# motadora.net
KiCad netlist of a schematic drawn in EAGLE
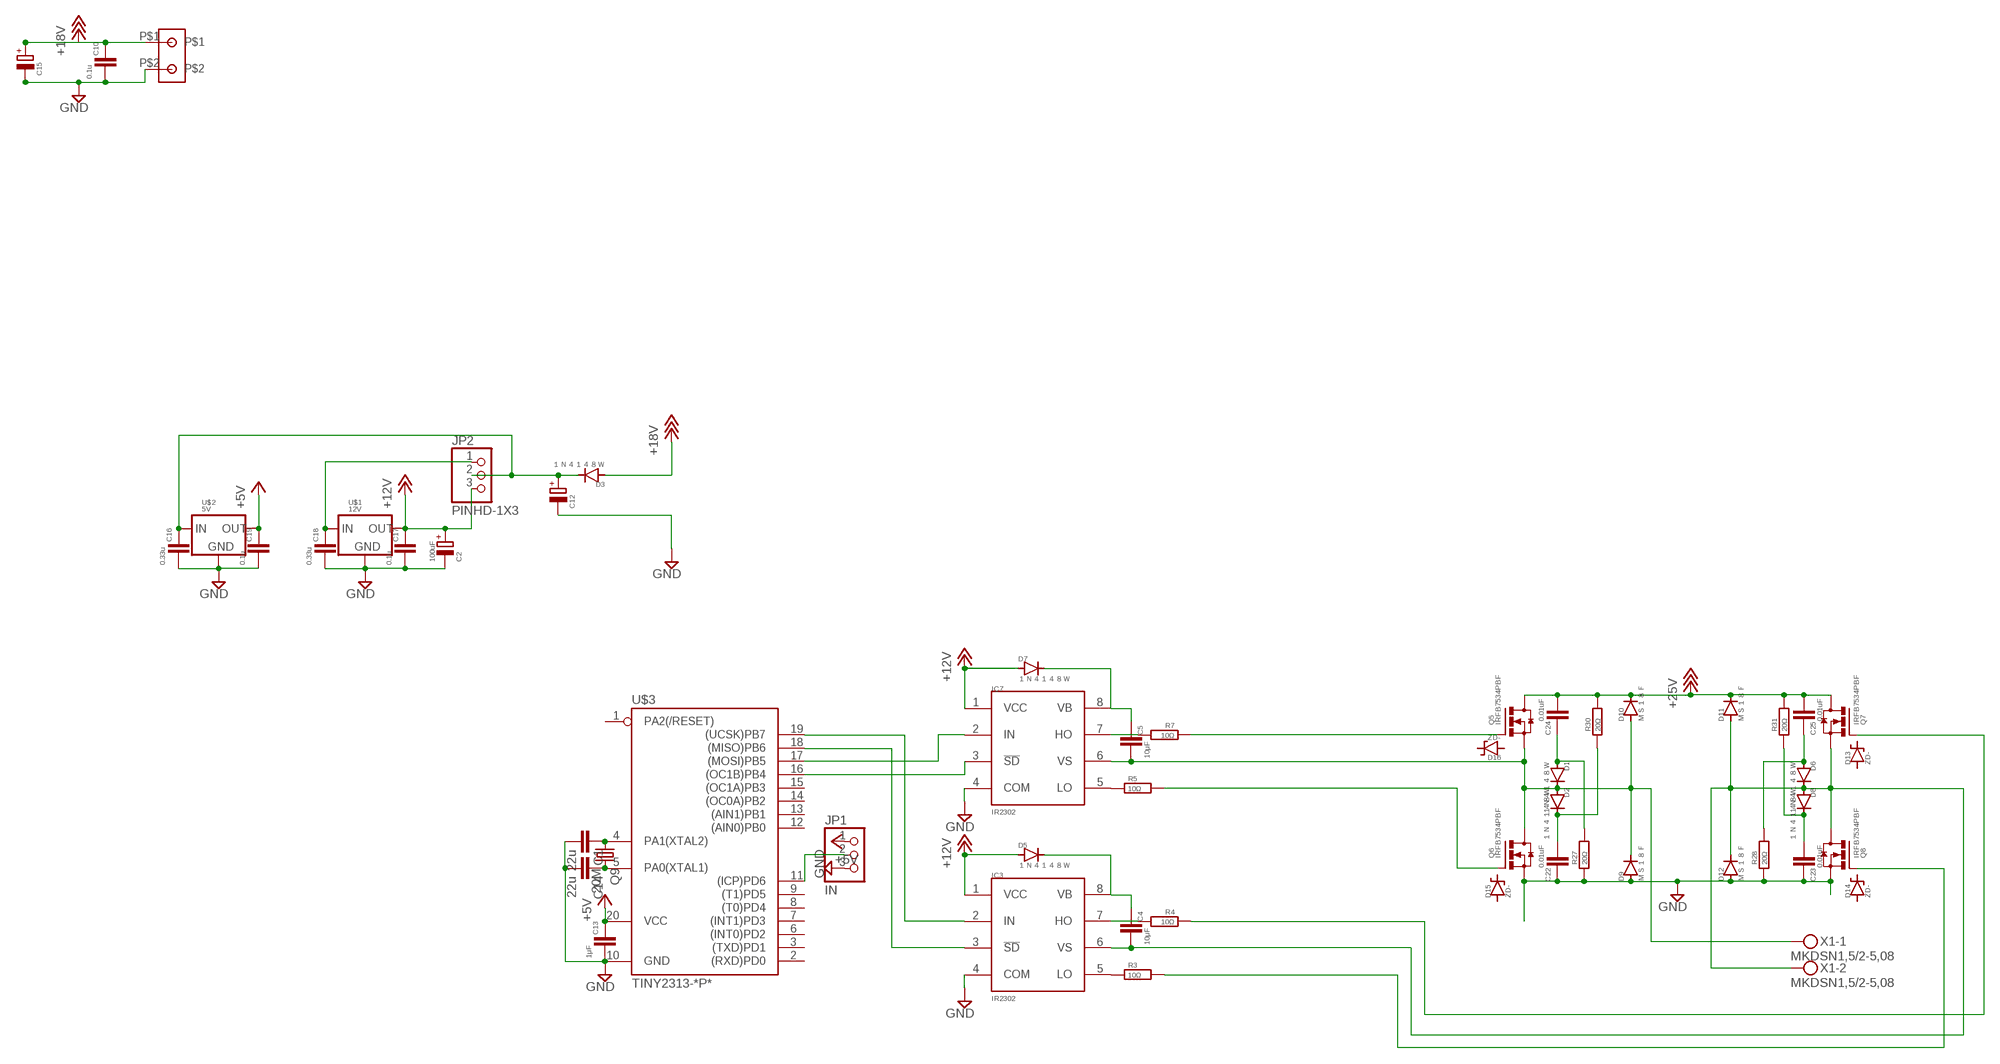
[diagram p0: schematic, sheet 1]

(export (version "E")
  (design (tool "Eeschema 10.0.6"))
  (components
    (comp (ref "C1")
      (value "22u")
      (footprint "eagle-import:C025-024X044")
      (libsource (lib "eagle-import") (part "_rcl_C-EU025-024X044"))
    )
    (comp (ref "C2")
      (value "100uF")
      (footprint "eagle-import:E2,5-7")
      (libsource (lib "eagle-import") (part "CPOL-EUE2.5-7"))
    )
    (comp (ref "C4")
      (value "10μF")
      (footprint "eagle-import:C050-024X044")
      (libsource (lib "eagle-import") (part "C-EU050-024X044"))
    )
    (comp (ref "C5")
      (value "10μF")
      (footprint "eagle-import:C050-024X044")
      (libsource (lib "eagle-import") (part "C-EU050-024X044"))
    )
    (comp (ref "C10")
      (value "0.1u")
      (footprint "eagle-import:2012")
      (libsource (lib "eagle-import") (part "_diode2_C-2012"))
    )
    (comp (ref "C12")
      (value "CPOL-EUE2.5-7")
      (footprint "eagle-import:E2,5-7")
      (libsource (lib "eagle-import") (part "CPOL-EUE2.5-7"))
    )
    (comp (ref "C13")
      (value "1μF")
      (footprint "eagle-import:C050-024X044")
      (libsource (lib "eagle-import") (part "C-EU050-024X044"))
    )
    (comp (ref "C14")
      (value "22u")
      (footprint "eagle-import:C025-024X044")
      (libsource (lib "eagle-import") (part "_rcl_C-EU025-024X044"))
    )
    (comp (ref "C15")
      (value "CPOL-EUE2.5-7")
      (footprint "eagle-import:E2,5-7")
      (libsource (lib "eagle-import") (part "CPOL-EUE2.5-7"))
    )
    (comp (ref "C16")
      (value "0.33u")
      (footprint "eagle-import:2012")
      (libsource (lib "eagle-import") (part "C-2012"))
    )
    (comp (ref "C17")
      (value "0.1u")
      (footprint "eagle-import:2012")
      (libsource (lib "eagle-import") (part "C-2012"))
    )
    (comp (ref "C18")
      (value "0.33u")
      (footprint "eagle-import:2012")
      (libsource (lib "eagle-import") (part "C-2012"))
    )
    (comp (ref "C19")
      (value "0.1u")
      (footprint "eagle-import:2012")
      (libsource (lib "eagle-import") (part "C-2012"))
    )
    (comp (ref "C22")
      (value "0.01uF")
      (footprint "eagle-import:2012")
      (libsource (lib "eagle-import") (part "C2012"))
    )
    (comp (ref "C23")
      (value "0.01uF")
      (footprint "eagle-import:2012")
      (libsource (lib "eagle-import") (part "_diode2_C-2012"))
    )
    (comp (ref "C24")
      (value "0.01uF")
      (footprint "eagle-import:2012")
      (libsource (lib "eagle-import") (part "C2012"))
    )
    (comp (ref "C25")
      (value "0.01uF")
      (footprint "eagle-import:2012")
      (libsource (lib "eagle-import") (part "_diode2_C-2012"))
    )
    (comp (ref "D1")
      (value "１Ｎ４１４８Ｗ")
      (footprint "eagle-import:SOD123")
      (libsource (lib "eagle-import") (part "D-SOD123"))
    )
    (comp (ref "D2")
      (value "１Ｎ４１４８Ｗ")
      (footprint "eagle-import:SOD123")
      (libsource (lib "eagle-import") (part "D-SOD123"))
    )
    (comp (ref "D3")
      (value "１Ｎ４１４８Ｗ")
      (footprint "eagle-import:D-7.5")
      (libsource (lib "eagle-import") (part "DIODE-D-7.5"))
    )
    (comp (ref "D5")
      (value "１Ｎ４１４８Ｗ")
      (footprint "eagle-import:D-7.5")
      (libsource (lib "eagle-import") (part "DIODE-D-7.5"))
    )
    (comp (ref "D6")
      (value "１Ｎ４１４８Ｗ")
      (footprint "eagle-import:SOD123")
      (libsource (lib "eagle-import") (part "D-SOD123"))
    )
    (comp (ref "D7")
      (value "１Ｎ４１４８Ｗ")
      (footprint "eagle-import:D-7.5")
      (libsource (lib "eagle-import") (part "DIODE-D-7.5"))
    )
    (comp (ref "D8")
      (value "１Ｎ４１４８Ｗ")
      (footprint "eagle-import:SOD123")
      (libsource (lib "eagle-import") (part "D-SOD123"))
    )
    (comp (ref "D9")
      (value "ＭＳ１８Ｆ")
      (footprint "eagle-import:^MS18F")
      (libsource (lib "eagle-import") (part "D-^MS18F"))
    )
    (comp (ref "D10")
      (value "ＭＳ１８Ｆ")
      (footprint "eagle-import:^MS18F")
      (libsource (lib "eagle-import") (part "D-^MS18F"))
    )
    (comp (ref "D11")
      (value "ＭＳ１８Ｆ")
      (footprint "eagle-import:^MS18F")
      (libsource (lib "eagle-import") (part "D-^MS18F"))
    )
    (comp (ref "D12")
      (value "ＭＳ１８Ｆ")
      (footprint "eagle-import:^MS18F")
      (libsource (lib "eagle-import") (part "D-^MS18F"))
    )
    (comp (ref "D13")
      (value "ZD-")
      (footprint "eagle-import:^U1ZB")
      (libsource (lib "eagle-import") (part "ZD-"))
    )
    (comp (ref "D14")
      (value "ZD-")
      (footprint "eagle-import:^U1ZB")
      (libsource (lib "eagle-import") (part "ZD-"))
    )
    (comp (ref "D15")
      (value "ZD-")
      (footprint "eagle-import:^U1ZB")
      (libsource (lib "eagle-import") (part "ZD-"))
    )
    (comp (ref "D16")
      (value "ZD-")
      (footprint "eagle-import:^U1ZB")
      (libsource (lib "eagle-import") (part "ZD-"))
    )
    (comp (ref "IC3")
      (value "IR2302")
      (footprint "eagle-import:DIL08")
      (libsource (lib "eagle-import") (part "IR2302IR2302"))
    )
    (comp (ref "IC7")
      (value "IR2302")
      (footprint "eagle-import:DIL08")
      (libsource (lib "eagle-import") (part "IR2302IR2302"))
    )
    (comp (ref "JP1")
      (value "IN")
      (footprint "eagle-import:1X03")
      (libsource (lib "eagle-import") (part "PINHD-1X3"))
    )
    (comp (ref "JP2")
      (value "PINHD-1X3")
      (footprint "eagle-import:1X03")
      (libsource (lib "eagle-import") (part "PINHD-1X3"))
    )
    (comp (ref "Q5")
      (value "IRFB7534PBF")
      (footprint "eagle-import:D2PACK")
      (libsource (lib "eagle-import") (part "MOS-FET_N(D2PACK)"))
    )
    (comp (ref "Q6")
      (value "IRFB7534PBF")
      (footprint "eagle-import:D2PACK")
      (libsource (lib "eagle-import") (part "MOS-FET_N(D2PACK)"))
    )
    (comp (ref "Q7")
      (value "IRFB7534PBF")
      (footprint "eagle-import:D2PACK")
      (libsource (lib "eagle-import") (part "MOS-FET_N(D2PACK)"))
    )
    (comp (ref "Q8")
      (value "IRFB7534PBF")
      (footprint "eagle-import:D2PACK")
      (libsource (lib "eagle-import") (part "MOS-FET_N(D2PACK)"))
    )
    (comp (ref "Q9")
      (value "20M")
      (footprint "eagle-import:HC49_S")
      (libsource (lib "eagle-import") (part "CRYSTALHC49S"))
    )
    (comp (ref "R3")
      (value "10Ω")
      (footprint "eagle-import:2012")
      (libsource (lib "eagle-import") (part "R-"))
    )
    (comp (ref "R4")
      (value "10Ω")
      (footprint "eagle-import:2012")
      (libsource (lib "eagle-import") (part "R-"))
    )
    (comp (ref "R5")
      (value "10Ω")
      (footprint "eagle-import:2012")
      (libsource (lib "eagle-import") (part "R-"))
    )
    (comp (ref "R7")
      (value "10Ω")
      (footprint "eagle-import:2012")
      (libsource (lib "eagle-import") (part "R-"))
    )
    (comp (ref "R27")
      (value "20Ω")
      (footprint "eagle-import:2012")
      (libsource (lib "eagle-import") (part "R-"))
    )
    (comp (ref "R28")
      (value "20Ω")
      (footprint "eagle-import:2012")
      (libsource (lib "eagle-import") (part "R-"))
    )
    (comp (ref "R30")
      (value "20Ω")
      (footprint "eagle-import:2012")
      (libsource (lib "eagle-import") (part "R-"))
    )
    (comp (ref "R31")
      (value "20Ω")
      (footprint "eagle-import:2012")
      (libsource (lib "eagle-import") (part "R-"))
    )
    (comp (ref "T1")
      (value "TANSIDAI")
      (footprint "eagle-import:A")
      (libsource (lib "eagle-import") (part "TANSIDAI"))
    )
    (comp (ref "U$1")
      (value "12V")
      (footprint "eagle-import:SOT-89")
      (libsource (lib "eagle-import") (part "V-REG(SOT-89)"))
    )
    (comp (ref "U$2")
      (value "5V")
      (footprint "eagle-import:SOT-89")
      (libsource (lib "eagle-import") (part "V-REG(SOT-89)"))
    )
    (comp (ref "U$3")
      (value "TINY2313-*P*")
      (footprint "eagle-import:DIL20")
      (libsource (lib "eagle-import") (part "TINY2313-P"))
    )
    (comp (ref "X1")
      (value "MKDSN1,5/2-5,08")
      (footprint "eagle-import:MKDSN1,5_2-5,08")
      (fields (field (name "MPN") "MKDSN 1,5/2-5.08"))
      (libsource (lib "eagle-import") (part "MKDSN1,5/2-5,08"))
    )
  )
  (nets
    (net (code "1") (name "+5V") (class "Default")
      (node (ref "C13") (pin "1") (pinfunction "1_1") (pintype "passive"))
      (node (ref "C19") (pin "1") (pinfunction "1_1") (pintype "passive"))
      (node (ref "JP1") (pin "1") (pinfunction "1_1") (pintype "passive"))
      (node (ref "U$2") (pin "1") (pinfunction "OUT_1") (pintype "passive"))
      (node (ref "U$3") (pin "20") (pinfunction "VCC_20") (pintype "power_in"))
    )
    (net (code "2") (name "+12V") (class "Default")
      (node (ref "C17") (pin "1") (pinfunction "1_1") (pintype "passive"))
      (node (ref "C2") (pin "+") (pinfunction "+_+") (pintype "passive"))
      (node (ref "D5") (pin "A") (pinfunction "A_A") (pintype "passive"))
      (node (ref "D7") (pin "A") (pinfunction "A_A") (pintype "passive"))
      (node (ref "IC3") (pin "1") (pinfunction "VCC_1") (pintype "bidirectional"))
      (node (ref "IC7") (pin "1") (pinfunction "VCC_1") (pintype "bidirectional"))
      (node (ref "JP2") (pin "3") (pinfunction "3_3") (pintype "passive"))
      (node (ref "U$1") (pin "1") (pinfunction "OUT_1") (pintype "passive"))
    )
    (net (code "3") (name "+18V") (class "Default")
      (node (ref "C10") (pin "1") (pinfunction "1_1") (pintype "passive"))
      (node (ref "C15") (pin "+") (pinfunction "+_+") (pintype "passive"))
      (node (ref "C24") (pin "2") (pinfunction "2_2") (pintype "passive"))
      (node (ref "C25") (pin "2") (pinfunction "2_2") (pintype "passive"))
      (node (ref "D10") (pin "CATHODE") (pinfunction "C_CATHODE") (pintype "passive"))
      (node (ref "D11") (pin "CATHODE") (pinfunction "C_CATHODE") (pintype "passive"))
      (node (ref "D3") (pin "A") (pinfunction "A_A") (pintype "passive"))
      (node (ref "Q5") (pin "2") (pinfunction "D_2") (pintype "passive"))
      (node (ref "Q7") (pin "2") (pinfunction "D_2") (pintype "passive"))
      (node (ref "R30") (pin "2") (pinfunction "2_2") (pintype "passive"))
      (node (ref "R31") (pin "2") (pinfunction "2_2") (pintype "passive"))
      (node (ref "T1") (pin "P$1") (pinfunction "P$1_P$1") (pintype "bidirectional"))
    )
    (net (code "4") (name "GND") (class "Default")
      (node (ref "C1") (pin "2") (pinfunction "2_2") (pintype "passive"))
      (node (ref "C10") (pin "2") (pinfunction "2_2") (pintype "passive"))
      (node (ref "C12") (pin "-") (pinfunction "-_-") (pintype "passive"))
      (node (ref "C13") (pin "2") (pinfunction "2_2") (pintype "passive"))
      (node (ref "C14") (pin "2") (pinfunction "2_2") (pintype "passive"))
      (node (ref "C15") (pin "-") (pinfunction "-_-") (pintype "passive"))
      (node (ref "C16") (pin "2") (pinfunction "2_2") (pintype "passive"))
      (node (ref "C17") (pin "2") (pinfunction "2_2") (pintype "passive"))
      (node (ref "C18") (pin "2") (pinfunction "2_2") (pintype "passive"))
      (node (ref "C19") (pin "2") (pinfunction "2_2") (pintype "passive"))
      (node (ref "C2") (pin "-") (pinfunction "-_-") (pintype "passive"))
      (node (ref "C22") (pin "1") (pinfunction "1_1") (pintype "passive"))
      (node (ref "C23") (pin "1") (pinfunction "1_1") (pintype "passive"))
      (node (ref "D12") (pin "ANODE") (pinfunction "A_ANODE") (pintype "passive"))
      (node (ref "D9") (pin "ANODE") (pinfunction "A_ANODE") (pintype "passive"))
      (node (ref "IC3") (pin "4") (pinfunction "COM_4") (pintype "bidirectional"))
      (node (ref "IC7") (pin "4") (pinfunction "COM_4") (pintype "bidirectional"))
      (node (ref "JP1") (pin "3") (pinfunction "3_3") (pintype "passive"))
      (node (ref "Q6") (pin "3") (pinfunction "S_3") (pintype "passive"))
      (node (ref "Q8") (pin "3") (pinfunction "S_3") (pintype "passive"))
      (node (ref "R27") (pin "1") (pinfunction "1_1") (pintype "passive"))
      (node (ref "R28") (pin "1") (pinfunction "1_1") (pintype "passive"))
      (node (ref "T1") (pin "P$2") (pinfunction "P$2_P$2") (pintype "bidirectional"))
      (node (ref "U$1") (pin "2") (pinfunction "GND_2") (pintype "input"))
      (node (ref "U$2") (pin "2") (pinfunction "GND_2") (pintype "input"))
      (node (ref "U$3") (pin "10") (pinfunction "GND_10") (pintype "power_in"))
    )
    (net (code "5") (name "Net-(C22-Pad2)") (class "Default")
      (node (ref "C22") (pin "2") (pinfunction "2_2") (pintype "passive"))
      (node (ref "D2") (pin "C") (pinfunction "C_C") (pintype "passive"))
      (node (ref "R30") (pin "1") (pinfunction "1_1") (pintype "passive"))
    )
    (net (code "6") (name "Net-(C23-Pad2)") (class "Default")
      (node (ref "C23") (pin "2") (pinfunction "2_2") (pintype "passive"))
      (node (ref "D8") (pin "C") (pinfunction "C_C") (pintype "passive"))
      (node (ref "R31") (pin "1") (pinfunction "1_1") (pintype "passive"))
    )
    (net (code "7") (name "Net-(C24-Pad1)") (class "Default")
      (node (ref "C24") (pin "1") (pinfunction "1_1") (pintype "passive"))
      (node (ref "D1") (pin "A") (pinfunction "A_A") (pintype "passive"))
      (node (ref "R27") (pin "2") (pinfunction "2_2") (pintype "passive"))
    )
    (net (code "8") (name "Net-(C25-Pad1)") (class "Default")
      (node (ref "C25") (pin "1") (pinfunction "1_1") (pintype "passive"))
      (node (ref "D6") (pin "A") (pinfunction "A_A") (pintype "passive"))
      (node (ref "R28") (pin "2") (pinfunction "2_2") (pintype "passive"))
    )
    (net (code "9") (name "Net-(D10-A)") (class "Default")
      (node (ref "C5") (pin "2") (pinfunction "2_2") (pintype "passive"))
      (node (ref "D1") (pin "C") (pinfunction "C_C") (pintype "passive"))
      (node (ref "D10") (pin "ANODE") (pinfunction "A_ANODE") (pintype "passive"))
      (node (ref "D2") (pin "A") (pinfunction "A_A") (pintype "passive"))
      (node (ref "D9") (pin "CATHODE") (pinfunction "C_CATHODE") (pintype "passive"))
      (node (ref "IC7") (pin "6") (pinfunction "VS_6") (pintype "bidirectional"))
      (node (ref "Q5") (pin "3") (pinfunction "S_3") (pintype "passive"))
      (node (ref "Q6") (pin "2") (pinfunction "D_2") (pintype "passive"))
      (node (ref "X1") (pin "1") (pinfunction "KL_1") (pintype "passive"))
    )
    (net (code "10") (name "Net-(D11-A)") (class "Default")
      (node (ref "C4") (pin "2") (pinfunction "2_2") (pintype "passive"))
      (node (ref "D11") (pin "ANODE") (pinfunction "A_ANODE") (pintype "passive"))
      (node (ref "D12") (pin "CATHODE") (pinfunction "C_CATHODE") (pintype "passive"))
      (node (ref "D6") (pin "C") (pinfunction "C_C") (pintype "passive"))
      (node (ref "D8") (pin "A") (pinfunction "A_A") (pintype "passive"))
      (node (ref "IC3") (pin "6") (pinfunction "VS_6") (pintype "bidirectional"))
      (node (ref "Q7") (pin "3") (pinfunction "S_3") (pintype "passive"))
      (node (ref "Q8") (pin "2") (pinfunction "D_2") (pintype "passive"))
      (node (ref "X1") (pin "2") (pinfunction "KL_2") (pintype "passive"))
    )
    (net (code "11") (name "Net-(IC3-HO)") (class "Default")
      (node (ref "IC3") (pin "7") (pinfunction "HO_7") (pintype "bidirectional"))
      (node (ref "R4") (pin "2") (pinfunction "2_2") (pintype "passive"))
    )
    (net (code "12") (name "Net-(IC3-IN)") (class "Default")
      (node (ref "IC3") (pin "2") (pinfunction "IN_2") (pintype "bidirectional"))
      (node (ref "U$3") (pin "19") (pinfunction "(UCSK)PB7_19") (pintype "bidirectional"))
    )
    (net (code "13") (name "Net-(IC3-LO)") (class "Default")
      (node (ref "IC3") (pin "5") (pinfunction "LO_5") (pintype "bidirectional"))
      (node (ref "R3") (pin "1") (pinfunction "1_1") (pintype "passive"))
    )
    (net (code "14") (name "Net-(IC3-VB)") (class "Default")
      (node (ref "C4") (pin "1") (pinfunction "1_1") (pintype "passive"))
      (node (ref "D5") (pin "C") (pinfunction "C_C") (pintype "passive"))
      (node (ref "IC3") (pin "8") (pinfunction "VB_8") (pintype "bidirectional"))
    )
    (net (code "15") (name "Net-(IC3-~{SD})") (class "Default")
      (node (ref "IC3") (pin "3") (pinfunction "~{SD}_3") (pintype "bidirectional"))
      (node (ref "U$3") (pin "18") (pinfunction "(MISO)PB6_18") (pintype "bidirectional"))
    )
    (net (code "16") (name "Net-(IC7-HO)") (class "Default")
      (node (ref "IC7") (pin "7") (pinfunction "HO_7") (pintype "bidirectional"))
      (node (ref "R7") (pin "2") (pinfunction "2_2") (pintype "passive"))
    )
    (net (code "17") (name "Net-(IC7-IN)") (class "Default")
      (node (ref "IC7") (pin "2") (pinfunction "IN_2") (pintype "bidirectional"))
      (node (ref "U$3") (pin "17") (pinfunction "(MOSI)PB5_17") (pintype "bidirectional"))
    )
    (net (code "18") (name "Net-(IC7-LO)") (class "Default")
      (node (ref "IC7") (pin "5") (pinfunction "LO_5") (pintype "bidirectional"))
      (node (ref "R5") (pin "1") (pinfunction "1_1") (pintype "passive"))
    )
    (net (code "19") (name "Net-(IC7-VB)") (class "Default")
      (node (ref "C5") (pin "1") (pinfunction "1_1") (pintype "passive"))
      (node (ref "D7") (pin "C") (pinfunction "C_C") (pintype "passive"))
      (node (ref "IC7") (pin "8") (pinfunction "VB_8") (pintype "bidirectional"))
    )
    (net (code "20") (name "Net-(IC7-~{SD})") (class "Default")
      (node (ref "IC7") (pin "3") (pinfunction "~{SD}_3") (pintype "bidirectional"))
      (node (ref "U$3") (pin "16") (pinfunction "(OC1B)PB4_16") (pintype "bidirectional"))
    )
    (net (code "21") (name "Net-(Q5-G)") (class "Default")
      (node (ref "Q5") (pin "1") (pinfunction "G_1") (pintype "passive"))
      (node (ref "R7") (pin "1") (pinfunction "1_1") (pintype "passive"))
    )
    (net (code "22") (name "Net-(Q6-G)") (class "Default")
      (node (ref "Q6") (pin "1") (pinfunction "G_1") (pintype "passive"))
      (node (ref "R5") (pin "2") (pinfunction "2_2") (pintype "passive"))
    )
    (net (code "23") (name "Net-(Q7-G)") (class "Default")
      (node (ref "Q7") (pin "1") (pinfunction "G_1") (pintype "passive"))
      (node (ref "R4") (pin "1") (pinfunction "1_1") (pintype "passive"))
    )
    (net (code "24") (name "Net-(Q8-G)") (class "Default")
      (node (ref "Q8") (pin "1") (pinfunction "G_1") (pintype "passive"))
      (node (ref "R3") (pin "2") (pinfunction "2_2") (pintype "passive"))
    )
    (net (code "25") (name "Net-(U$1-IN)") (class "Default")
      (node (ref "C18") (pin "1") (pinfunction "1_1") (pintype "passive"))
      (node (ref "JP2") (pin "1") (pinfunction "1_1") (pintype "passive"))
      (node (ref "U$1") (pin "3") (pinfunction "IN_3") (pintype "input"))
    )
    (net (code "26") (name "Net-(U$2-IN)") (class "Default")
      (node (ref "C12") (pin "+") (pinfunction "+_+") (pintype "passive"))
      (node (ref "C16") (pin "1") (pinfunction "1_1") (pintype "passive"))
      (node (ref "D3") (pin "C") (pinfunction "C_C") (pintype "passive"))
      (node (ref "JP2") (pin "2") (pinfunction "2_2") (pintype "passive"))
      (node (ref "U$2") (pin "3") (pinfunction "IN_3") (pintype "input"))
    )
    (net (code "27") (name "Net-(U$3-(ICP)PD6)") (class "Default")
      (node (ref "JP1") (pin "2") (pinfunction "2_2") (pintype "passive"))
      (node (ref "U$3") (pin "11") (pinfunction "(ICP)PD6_11") (pintype "bidirectional"))
    )
    (net (code "28") (name "Net-(U$3-PA0(XTAL1))") (class "Default")
      (node (ref "C14") (pin "1") (pinfunction "1_1") (pintype "passive"))
      (node (ref "Q9") (pin "2") (pinfunction "2_2") (pintype "passive"))
      (node (ref "U$3") (pin "5") (pinfunction "PA0(XTAL1)_5") (pintype "bidirectional"))
    )
    (net (code "29") (name "Net-(U$3-PA1(XTAL2))") (class "Default")
      (node (ref "C1") (pin "1") (pinfunction "1_1") (pintype "passive"))
      (node (ref "Q9") (pin "1") (pinfunction "1_1") (pintype "passive"))
      (node (ref "U$3") (pin "4") (pinfunction "PA1(XTAL2)_4") (pintype "bidirectional"))
    )
    (net (code "30") (name "unconnected-(D13-A-PadANODE)") (class "Default")
      (node (ref "D13") (pin "ANODE") (pinfunction "A_ANODE") (pintype "passive"))
    )
    (net (code "31") (name "unconnected-(D13-C-PadCATHODE)") (class "Default")
      (node (ref "D13") (pin "CATHODE") (pinfunction "C_CATHODE") (pintype "passive"))
    )
    (net (code "32") (name "unconnected-(D14-A-PadANODE)") (class "Default")
      (node (ref "D14") (pin "ANODE") (pinfunction "A_ANODE") (pintype "passive"))
    )
    (net (code "33") (name "unconnected-(D14-C-PadCATHODE)") (class "Default")
      (node (ref "D14") (pin "CATHODE") (pinfunction "C_CATHODE") (pintype "passive"))
    )
    (net (code "34") (name "unconnected-(D15-A-PadANODE)") (class "Default")
      (node (ref "D15") (pin "ANODE") (pinfunction "A_ANODE") (pintype "passive"))
    )
    (net (code "35") (name "unconnected-(D15-C-PadCATHODE)") (class "Default")
      (node (ref "D15") (pin "CATHODE") (pinfunction "C_CATHODE") (pintype "passive"))
    )
    (net (code "36") (name "unconnected-(D16-A-PadANODE)") (class "Default")
      (node (ref "D16") (pin "ANODE") (pinfunction "A_ANODE") (pintype "passive"))
    )
    (net (code "37") (name "unconnected-(D16-C-PadCATHODE)") (class "Default")
      (node (ref "D16") (pin "CATHODE") (pinfunction "C_CATHODE") (pintype "passive"))
    )
    (net (code "38") (name "unconnected-(U$3-(AIN0)PB0-Pad12)") (class "Default")
      (node (ref "U$3") (pin "12") (pinfunction "(AIN0)PB0_12") (pintype "bidirectional"))
    )
    (net (code "39") (name "unconnected-(U$3-(AIN1)PB1-Pad13)") (class "Default")
      (node (ref "U$3") (pin "13") (pinfunction "(AIN1)PB1_13") (pintype "bidirectional"))
    )
    (net (code "40") (name "unconnected-(U$3-(INT0)PD2-Pad6)") (class "Default")
      (node (ref "U$3") (pin "6") (pinfunction "(INT0)PD2_6") (pintype "bidirectional"))
    )
    (net (code "41") (name "unconnected-(U$3-(INT1)PD3-Pad7)") (class "Default")
      (node (ref "U$3") (pin "7") (pinfunction "(INT1)PD3_7") (pintype "bidirectional"))
    )
    (net (code "42") (name "unconnected-(U$3-(OC0A)PB2-Pad14)") (class "Default")
      (node (ref "U$3") (pin "14") (pinfunction "(OC0A)PB2_14") (pintype "bidirectional"))
    )
    (net (code "43") (name "unconnected-(U$3-(OC1A)PB3-Pad15)") (class "Default")
      (node (ref "U$3") (pin "15") (pinfunction "(OC1A)PB3_15") (pintype "bidirectional"))
    )
    (net (code "44") (name "unconnected-(U$3-(RXD)PD0-Pad2)") (class "Default")
      (node (ref "U$3") (pin "2") (pinfunction "(RXD)PD0_2") (pintype "bidirectional"))
    )
    (net (code "45") (name "unconnected-(U$3-(T0)PD4-Pad8)") (class "Default")
      (node (ref "U$3") (pin "8") (pinfunction "(T0)PD4_8") (pintype "bidirectional"))
    )
    (net (code "46") (name "unconnected-(U$3-(T1)PD5-Pad9)") (class "Default")
      (node (ref "U$3") (pin "9") (pinfunction "(T1)PD5_9") (pintype "bidirectional"))
    )
    (net (code "47") (name "unconnected-(U$3-(TXD)PD1-Pad3)") (class "Default")
      (node (ref "U$3") (pin "3") (pinfunction "(TXD)PD1_3") (pintype "bidirectional"))
    )
    (net (code "48") (name "unconnected-(U$3-PA2({slash}RESET)-Pad1)") (class "Default")
      (node (ref "U$3") (pin "1") (pinfunction "PA2(/RESET)_1") (pintype "input"))
    )
  )
)
